# ChannelDriver.net
KiCad netlist of a schematic drawn in Altium Designer
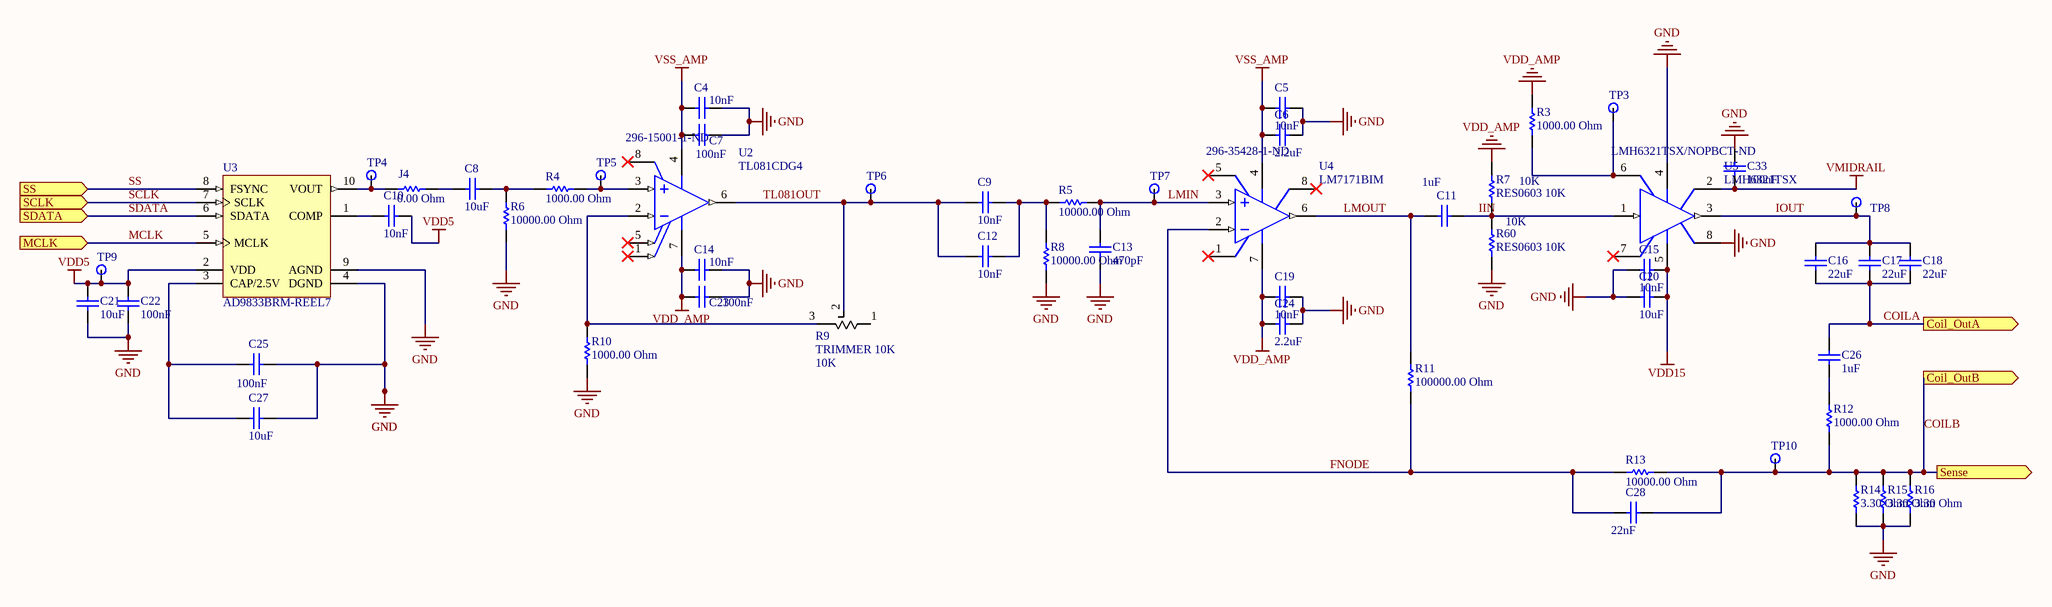
[diagram p0: ChannelDriver.SchDoc]

(export (version "E")
  (design (tool "Eeschema 10.0.6"))
  (components
    (comp (ref "C4")
      (value "10nF")
      (footprint "CAPC0603(1608)100_N")
      (description "CAP 10nF 25V ±10% 0603 (1608 Metric) Thickness 1mm SMD")
      (fields (field (name "TOLERANCE") "Â±10%") (field (name "Comment") "CAP 10nF 25V 0603(1608)"))
      (libsource (lib "Altium Content Vault") (part "CMP-1035-02317-1"))
    )
    (comp (ref "C5")
      (value "10nF")
      (footprint "CAPC0603(1608)100_N")
      (description "CAP 10nF 25V ±10% 0603 (1608 Metric) Thickness 1mm SMD")
      (fields (field (name "TOLERANCE") "Â±10%") (field (name "Comment") "CAP 10nF 25V 0603(1608)"))
      (libsource (lib "Altium Content Vault") (part "CMP-1035-02317-1"))
    )
    (comp (ref "C6")
      (value "2.2uF")
      (footprint "CAPC0603(1608)100_M")
      (description "CAP 2.2uF 25V ±10% 0603 (1608 Metric) Thickness 1mm SMD")
      (fields (field (name "TOLERANCE") "Â±10%") (field (name "MANUFACTURER") "Taiyo Yuden"))
      (libsource (lib "Altium Content Vault") (part "CMP-1035-02767-1"))
    )
    (comp (ref "C7")
      (value "100nF")
      (footprint "CAPC0603(1608)100_M")
      (description "CAP 100nF 25V ±10% 0603 (1608 Metric) Thickness 1mm SMD")
      (fields (field (name "TOLERANCE") "Â±10%") (field (name "Comment") "CAP 100nF 25V 0603(1608)"))
      (libsource (lib "Altium Content Vault") (part "CMP-1035-02588-1"))
    )
    (comp (ref "C8")
      (value "10uF")
      (footprint "CAPC1206(3216)190_L")
      (description "CAP 10uF 25V ±10% 1206 (3216 Metric) Thickness 1.9mm SMD")
      (fields (field (name "TOLERANCE") "Â±10%") (field (name "Comment") "CAP 10uF 25V 1206(3216)"))
      (libsource (lib "Altium Content Vault") (part "CMP-1037-04979-1"))
    )
    (comp (ref "C9")
      (value "10nF")
      (footprint "CAPC0603(1608)100_N")
      (description "CAP 10nF 25V ±10% 0603 (1608 Metric) Thickness 1mm SMD")
      (fields (field (name "TOLERANCE") "Â±10%") (field (name "Comment") "CAP 10nF 25V 0603(1608)"))
      (libsource (lib "Altium Content Vault") (part "CMP-1035-02317-1"))
    )
    (comp (ref "C10")
      (value "10nF")
      (footprint "CAPC0603(1608)100_N")
      (description "CAP 10nF 25V ±10% 0603 (1608 Metric) Thickness 1mm SMD")
      (fields (field (name "TOLERANCE") "Â±10%") (field (name "Comment") "CAP 10nF 25V 0603(1608)"))
      (libsource (lib "Altium Content Vault") (part "CMP-1035-02317-1"))
    )
    (comp (ref "C11")
      (value "1uF")
      (footprint "CAPC0603(1608)100_L")
      (description "CAP 1uF 25V ±10% 0603 (1608 Metric) Thickness 1mm SMD")
      (fields (field (name "TOLERANCE") "Â±10%") (field (name "Comment") "CAP 1uF 25V 0603(1608)"))
      (libsource (lib "Altium Content Vault") (part "CMP-1035-02740-1"))
    )
    (comp (ref "C12")
      (value "10nF")
      (footprint "CAPC0603(1608)100_N")
      (description "CAP 10nF 25V ±10% 0603 (1608 Metric) Thickness 1mm SMD")
      (fields (field (name "TOLERANCE") "Â±10%") (field (name "Comment") "CAP 10nF 25V 0603(1608)"))
      (libsource (lib "Altium Content Vault") (part "CMP-1035-02317-1"))
    )
    (comp (ref "C13")
      (value "470pF")
      (footprint "CAPC0603(1608)100_N")
      (description "CAP 470pF 25V ±10% 0603 (1608 Metric) Thickness 1mm SMD")
      (fields (field (name "TOLERANCE") "Â±10%") (field (name "MANUFACTURER") "KEMET"))
      (libsource (lib "Altium Content Vault") (part "CMP-1035-01671-1"))
    )
    (comp (ref "C14")
      (value "10nF")
      (footprint "CAPC0603(1608)100_N")
      (description "CAP 10nF 25V ±10% 0603 (1608 Metric) Thickness 1mm SMD")
      (fields (field (name "TOLERANCE") "Â±10%") (field (name "Comment") "CAP 10nF 25V 0603(1608)"))
      (libsource (lib "Altium Content Vault") (part "CMP-1035-02317-1"))
    )
    (comp (ref "C15")
      (value "10nF")
      (footprint "CAPC0603(1608)100_N")
      (description "CAP 10nF 25V ±10% 0603 (1608 Metric) Thickness 1mm SMD")
      (fields (field (name "TOLERANCE") "Â±10%") (field (name "Comment") "CAP 10nF 25V 0603(1608)"))
      (libsource (lib "Altium Content Vault") (part "CMP-1035-02317-1"))
    )
    (comp (ref "C16")
      (value "22uF")
      (footprint "CAPC1206(3216)190_M")
      (description "CAP 22uF 25V ±20% 1206 (3216 Metric) Thickness 1.9mm SMD")
      (fields (field (name "TOLERANCE") "Â±20%") (field (name "Comment") "CAP 22uF 25V 1206(3216)"))
      (libsource (lib "Altium Content Vault") (part "CMP-1037-04995-1"))
    )
    (comp (ref "C17")
      (value "22uF")
      (footprint "CAPC1206(3216)190_M")
      (description "CAP 22uF 25V ±20% 1206 (3216 Metric) Thickness 1.9mm SMD")
      (fields (field (name "TOLERANCE") "Â±20%") (field (name "Comment") "CAP 22uF 25V 1206(3216)"))
      (libsource (lib "Altium Content Vault") (part "CMP-1037-04995-1"))
    )
    (comp (ref "C18")
      (value "22uF")
      (footprint "CAPC1206(3216)190_M")
      (description "CAP 22uF 25V ±20% 1206 (3216 Metric) Thickness 1.9mm SMD")
      (fields (field (name "TOLERANCE") "Â±20%") (field (name "Comment") "CAP 22uF 25V 1206(3216)"))
      (libsource (lib "Altium Content Vault") (part "CMP-1037-04995-1"))
    )
    (comp (ref "C19")
      (value "10nF")
      (footprint "CAPC0603(1608)100_N")
      (description "CAP 10nF 25V ±10% 0603 (1608 Metric) Thickness 1mm SMD")
      (fields (field (name "TOLERANCE") "Â±10%") (field (name "Comment") "CAP 10nF 25V 0603(1608)"))
      (libsource (lib "Altium Content Vault") (part "CMP-1035-02317-1"))
    )
    (comp (ref "C20")
      (value "10uF")
      (footprint "CAPC1206(3216)190_L")
      (description "CAP 10uF 25V ±10% 1206 (3216 Metric) Thickness 1.9mm SMD")
      (fields (field (name "TOLERANCE") "Â±10%") (field (name "Comment") "CAP 10uF 25V 1206(3216)"))
      (libsource (lib "Altium Content Vault") (part "CMP-1037-04979-1"))
    )
    (comp (ref "C21")
      (value "10uF")
      (footprint "CAPC1206(3216)190_L")
      (description "CAP 10uF 25V ±10% 1206 (3216 Metric) Thickness 1.9mm SMD")
      (fields (field (name "TOLERANCE") "Â±10%") (field (name "Comment") "CAP 10uF 25V 1206(3216)"))
      (libsource (lib "Altium Content Vault") (part "CMP-1037-04979-1"))
    )
    (comp (ref "C22")
      (value "100nF")
      (footprint "CAPC0603(1608)100_M")
      (description "CAP 100nF 25V ±10% 0603 (1608 Metric) Thickness 1mm SMD")
      (fields (field (name "TOLERANCE") "Â±10%") (field (name "Comment") "CAP 100nF 25V 0603(1608)"))
      (libsource (lib "Altium Content Vault") (part "CMP-1035-02588-1"))
    )
    (comp (ref "C23")
      (value "100nF")
      (footprint "CAPC0603(1608)100_M")
      (description "CAP 100nF 25V ±10% 0603 (1608 Metric) Thickness 1mm SMD")
      (fields (field (name "TOLERANCE") "Â±10%") (field (name "Comment") "CAP 100nF 25V 0603(1608)"))
      (libsource (lib "Altium Content Vault") (part "CMP-1035-02588-1"))
    )
    (comp (ref "C24")
      (value "2.2uF")
      (footprint "CAPC0603(1608)100_M")
      (description "CAP 2.2uF 25V ±10% 0603 (1608 Metric) Thickness 1mm SMD")
      (fields (field (name "TOLERANCE") "Â±10%") (field (name "MANUFACTURER") "Taiyo Yuden"))
      (libsource (lib "Altium Content Vault") (part "CMP-1035-02767-1"))
    )
    (comp (ref "C25")
      (value "100nF")
      (footprint "CAPC0603(1608)100_M")
      (description "CAP 100nF 25V ±10% 0603 (1608 Metric) Thickness 1mm SMD")
      (fields (field (name "TOLERANCE") "Â±10%") (field (name "Comment") "CAP 100nF 25V 0603(1608)"))
      (libsource (lib "Altium Content Vault") (part "CMP-1035-02588-1"))
    )
    (comp (ref "C26")
      (value "1uF")
      (footprint "CAPC0603(1608)100_L")
      (description "CAP 1uF 25V ±10% 0603 (1608 Metric) Thickness 1mm SMD")
      (fields (field (name "TOLERANCE") "Â±10%") (field (name "Comment") "CAP 1uF 25V 0603(1608)"))
      (libsource (lib "Altium Content Vault") (part "CMP-1035-02740-1"))
    )
    (comp (ref "C27")
      (value "10uF")
      (footprint "CAPC1206(3216)190_L")
      (description "CAP 10uF 25V ±10% 1206 (3216 Metric) Thickness 1.9mm SMD")
      (fields (field (name "TOLERANCE") "Â±10%") (field (name "Comment") "CAP 10uF 25V 1206(3216)"))
      (libsource (lib "Altium Content Vault") (part "CMP-1037-04979-1"))
    )
    (comp (ref "C28")
      (value "22nF")
      (footprint "CAPC0603(1608)100_N")
      (description "CAP 10nF 25V ±10% 0603 (1608 Metric) Thickness 1mm SMD")
      (fields (field (name "TOLERANCE") "Â±10%") (field (name "MANUFACTURER") "Taiyo Yuden"))
      (libsource (lib "Altium Content Vault") (part "CMP-1035-02317-1"))
    )
    (comp (ref "C33")
      (value "100nF")
      (footprint "CAPC0603(1608)100_M")
      (description "CAP 100nF 25V ±10% 0603 (1608 Metric) Thickness 1mm SMD")
      (fields (field (name "TOLERANCE") "Â±10%") (field (name "Comment") "CAP 100nF 25V 0603(1608)"))
      (libsource (lib "Altium Content Vault") (part "CMP-1035-02588-1"))
    )
    (comp (ref "J4")
      (value "0.00 Ohm")
      (footprint "RESC1206(3216)_M")
      (description "Jumper 1206 (3216 Metric)")
      (fields (field (name "TOLERANCE") "None"))
      (libsource (lib "Altium Content Vault") (part "CMP-1014-00001-1"))
    )
    (comp (ref "R3")
      (value "1000.00 Ohm")
      (footprint "RESC0603(1608)_L")
      (description "1K 0.1W 5% 0603 (1608 Metric)  SMD")
      (fields (field (name "TOLERANCE") "5 %") (field (name "POWER") "0.1 W"))
      (libsource (lib "Altium Content Vault") (part "CMP-1012-00074-1"))
    )
    (comp (ref "R4")
      (value "1000.00 Ohm")
      (footprint "RESC0603(1608)_L")
      (description "1K 0.1W 5% 0603 (1608 Metric)  SMD")
      (fields (field (name "TOLERANCE") "5 %") (field (name "POWER") "0.1 W"))
      (libsource (lib "Altium Content Vault") (part "CMP-1012-00074-1"))
    )
    (comp (ref "R5")
      (value "10000.00 Ohm")
      (footprint "RESC0603(1608)_N")
      (description "10K 0.1W 5% 0603 (1608 Metric)  SMD")
      (fields (field (name "TOLERANCE") "5 %") (field (name "POWER") "0.1 W"))
      (libsource (lib "Altium Content Vault") (part "CMP-1012-00098-1"))
    )
    (comp (ref "R6")
      (value "10000.00 Ohm")
      (footprint "RESC0603(1608)_N")
      (description "10K 0.1W 5% 0603 (1608 Metric)  SMD")
      (fields (field (name "TOLERANCE") "5 %") (field (name "POWER") "0.1 W"))
      (libsource (lib "Altium Content Vault") (part "CMP-1012-00098-1"))
    )
    (comp (ref "R7")
      (value "RES0603 10K")
      (footprint "RESC0603(1608)_L")
      (description "0603 (1608 Metric) Chip Resistor")
      (fields
        (field (name "ALTIUM_VALUE") "10K")
        (field (name "MANUFACTURER") "Yageo")
        (field (name "MANUFACTURER PART NUMBER") "RT0603BRD0710KL")
      )
      (libsource (lib "Altium Content Vault") (part "CMP-1591-00001-1"))
    )
    (comp (ref "R8")
      (value "10000.00 Ohm")
      (footprint "RESC0603(1608)_N")
      (description "10K 0.1W 5% 0603 (1608 Metric)  SMD")
      (fields (field (name "TOLERANCE") "5 %") (field (name "POWER") "0.1 W"))
      (libsource (lib "Altium Content Vault") (part "CMP-1012-00098-1"))
    )
    (comp (ref "R9")
      (value "TRIMMER 10K")
      (footprint "TRIMMER 10K")
      (description "TRIMMER 10K OHM 0.5W TH")
      (fields
        (field (name "MANUFACTURER") "TE Connectivity Passive Product")
        (field (name "MANUFACTURER PART NUMBER") "1-1623849-0")
        (field (name "ALTIUM_VALUE") "10K")
        (field (name "PUBLISHER") "Altium Limited")
      )
      (libsource (lib "AnserEMT") (part "TRIMMER 10K"))
    )
    (comp (ref "R10")
      (value "1000.00 Ohm")
      (footprint "RESC0603(1608)_L")
      (description "1K 0.1W 5% 0603 (1608 Metric)  SMD")
      (fields (field (name "TOLERANCE") "5 %") (field (name "POWER") "0.1 W"))
      (libsource (lib "Altium Content Vault") (part "CMP-1012-00074-1"))
    )
    (comp (ref "R11")
      (value "100000.00 Ohm")
      (footprint "RESC0603(1608)_N")
      (description "100K 0.1W 5% 0603 (1608 Metric)  SMD")
      (fields (field (name "TOLERANCE") "5 %") (field (name "POWER") "0.1 W"))
      (libsource (lib "Altium Content Vault") (part "CMP-1012-00122-1"))
    )
    (comp (ref "R12")
      (value "1000.00 Ohm")
      (footprint "RESC0603(1608)_L")
      (description "1K 0.1W 5% 0603 (1608 Metric)  SMD")
      (fields (field (name "TOLERANCE") "5 %") (field (name "POWER") "0.1 W"))
      (libsource (lib "Altium Content Vault") (part "CMP-1012-00074-1"))
    )
    (comp (ref "R13")
      (value "10000.00 Ohm")
      (footprint "RESC0603(1608)_N")
      (description "10K 0.1W 5% 0603 (1608 Metric)  SMD")
      (fields (field (name "TOLERANCE") "5 %") (field (name "POWER") "0.1 W"))
      (libsource (lib "Altium Content Vault") (part "CMP-1012-00098-1"))
    )
    (comp (ref "R14")
      (value "3.30 Ohm")
      (footprint "RESC1206(3216)_N")
      (description "3R3 0.25W 5% 1206 (3216 Metric)  SMD")
      (fields (field (name "POWER") "0.25 W") (field (name "TOLERANCE") "5 %"))
      (libsource (lib "Altium Content Vault") (part "CMP-1014-00014-1"))
    )
    (comp (ref "R15")
      (value "3.30 Ohm")
      (footprint "RESC1206(3216)_N")
      (description "3R3 0.25W 5% 1206 (3216 Metric)  SMD")
      (fields (field (name "POWER") "0.25 W") (field (name "TOLERANCE") "5 %"))
      (libsource (lib "Altium Content Vault") (part "CMP-1014-00014-1"))
    )
    (comp (ref "R16")
      (value "3.30 Ohm")
      (footprint "RESC1206(3216)_N")
      (description "3R3 0.25W 5% 1206 (3216 Metric)  SMD")
      (fields (field (name "POWER") "0.25 W") (field (name "TOLERANCE") "5 %"))
      (libsource (lib "Altium Content Vault") (part "CMP-1014-00014-1"))
    )
    (comp (ref "R60")
      (value "RES0603 10K")
      (footprint "RESC0603(1608)_L")
      (description "0603 (1608 Metric) Chip Resistor")
      (fields
        (field (name "ALTIUM_VALUE") "10K")
        (field (name "MANUFACTURER") "Yageo")
        (field (name "MANUFACTURER PART NUMBER") "RT0603BRD0710KL")
      )
      (libsource (lib "Altium Content Vault") (part "CMP-1591-00001-1"))
    )
    (comp (ref "TP3")
      (value "Testpoint")
      (footprint "0603 PROBE PAD")
      (description "0.063\" x 0.031\" x 0.045\" (1.60mm x 0.80mm x 1.15mm)")
      (libsource (lib "testpoint") (part "Testpoint"))
    )
    (comp (ref "TP4")
      (value "Testpoint")
      (footprint "0603 PROBE PAD")
      (description "0.063\" x 0.031\" x 0.045\" (1.60mm x 0.80mm x 1.15mm)")
      (libsource (lib "testpoint") (part "Testpoint"))
    )
    (comp (ref "TP5")
      (value "Testpoint")
      (footprint "0603 PROBE PAD")
      (description "0.063\" x 0.031\" x 0.045\" (1.60mm x 0.80mm x 1.15mm)")
      (libsource (lib "testpoint") (part "Testpoint"))
    )
    (comp (ref "TP6")
      (value "Testpoint")
      (footprint "0603 PROBE PAD")
      (description "0.063\" x 0.031\" x 0.045\" (1.60mm x 0.80mm x 1.15mm)")
      (libsource (lib "testpoint") (part "Testpoint"))
    )
    (comp (ref "TP7")
      (value "Testpoint")
      (footprint "0603 PROBE PAD")
      (description "0.063\" x 0.031\" x 0.045\" (1.60mm x 0.80mm x 1.15mm)")
      (libsource (lib "testpoint") (part "Testpoint"))
    )
    (comp (ref "TP8")
      (value "Testpoint")
      (footprint "0603 PROBE PAD")
      (description "0.063\" x 0.031\" x 0.045\" (1.60mm x 0.80mm x 1.15mm)")
      (libsource (lib "testpoint") (part "Testpoint"))
    )
    (comp (ref "TP9")
      (value "Testpoint")
      (footprint "0603 PROBE PAD")
      (description "0.063\" x 0.031\" x 0.045\" (1.60mm x 0.80mm x 1.15mm)")
      (libsource (lib "testpoint") (part "Testpoint"))
    )
    (comp (ref "TP10")
      (value "Testpoint")
      (footprint "0603 PROBE PAD")
      (description "0.063\" x 0.031\" x 0.045\" (1.60mm x 0.80mm x 1.15mm)")
      (libsource (lib "testpoint") (part "Testpoint"))
    )
    (comp (ref "U2")
      (value "TL081CDG4")
      (footprint "TI-D8_N")
      (fields
        (field (name "MANUFACTURER") "Texas Instruments")
        (field (name "SUPPLIER PART NUMBER 1") "296-15001-1-ND")
        (field (name "MANUFACTURER PART NUMBER") "TL081CDR")
      )
      (libsource (lib "Altium Content Vault") (part "CMP-0017-00506-1"))
    )
    (comp (ref "U3")
      (value "AD9833BRM-REEL7")
      (footprint "ADI-RM-10_L")
      (fields
        (field (name "MANUFACTURER") "Analog Devices Inc.")
        (field (name "MANUFACTURER PART NUMBER") "AD9833BRMZ-REEL7")
      )
      (libsource (lib "Altium Content Vault") (part "CMP-0293-00080-1"))
    )
    (comp (ref "U4")
      (value "LM7171BIM")
      (footprint "D0008A_L")
      (description "Very High Speed, High Output Current, Voltage Feedback Amplifier, 8-pin Narrow SOIC")
      (fields
        (field (name "MANUFACTURER") "Texas Instruments")
        (field (name "SUPPLIER PART NUMBER 1") "296-35428-1-ND")
        (field (name "MANUFACTURER PART NUMBER") "LM7171AIMX/NOPB")
      )
      (libsource (lib "Altium Content Vault") (part "CMP-0055-00670-3"))
    )
    (comp (ref "U5")
      (value "LMH6321TSX")
      (footprint "TS7B_N")
      (description "300 mA High Speed Buffer with Adjustable Current Limit, 7-pin TO-263")
      (fields
        (field (name "MANUFACTURER") "National Semiconductor")
        (field (name "SUPPLIER PART NUMBER 1") "LMH6321TSX/NOPBCT-ND")
        (field (name "MANUFACTURER PART NUMBER") "LMH6321TSX/NOPB")
      )
      (libsource (lib "Altium Content Vault") (part "CMP-0055-00076-2"))
    )
  )
  (nets
    (net (code "1") (name "/COILA") (class "Default")
      (node (ref "C16") (pin "2") (pinfunction "2_2") (pintype "passive"))
      (node (ref "C17") (pin "2") (pinfunction "2_2") (pintype "passive"))
      (node (ref "C18") (pin "2") (pinfunction "2_2") (pintype "passive"))
      (node (ref "C26") (pin "2") (pinfunction "2_2") (pintype "passive"))
    )
    (net (code "2") (name "/COILB") (class "Default")
      (node (ref "C28") (pin "2") (pinfunction "2_2") (pintype "passive"))
      (node (ref "R12") (pin "2") (pinfunction "2_2") (pintype "passive"))
      (node (ref "R13") (pin "1") (pinfunction "1_1") (pintype "passive"))
      (node (ref "R14") (pin "2") (pinfunction "2_2") (pintype "passive"))
      (node (ref "R15") (pin "2") (pinfunction "2_2") (pintype "passive"))
      (node (ref "R16") (pin "2") (pinfunction "2_2") (pintype "passive"))
      (node (ref "TP10") (pin "0") (pintype "passive"))
    )
    (net (code "3") (name "/FNODE") (class "Default")
      (node (ref "C28") (pin "1") (pinfunction "1_1") (pintype "passive"))
      (node (ref "R11") (pin "2") (pinfunction "2_2") (pintype "passive"))
      (node (ref "R13") (pin "2") (pinfunction "2_2") (pintype "passive"))
      (node (ref "U4") (pin "2") (pinfunction "IN-_2") (pintype "input"))
    )
    (net (code "4") (name "/IIN") (class "Default")
      (node (ref "C11") (pin "2") (pinfunction "2_2") (pintype "passive"))
      (node (ref "R60") (pin "2") (pinfunction "2_2") (pintype "passive"))
      (node (ref "R7") (pin "1") (pinfunction "1_1") (pintype "passive"))
      (node (ref "U5") (pin "1") (pinfunction "IN_1") (pintype "input"))
    )
    (net (code "5") (name "/IOUT") (class "Default")
      (node (ref "C16") (pin "1") (pinfunction "1_1") (pintype "passive"))
      (node (ref "C17") (pin "1") (pinfunction "1_1") (pintype "passive"))
      (node (ref "C18") (pin "1") (pinfunction "1_1") (pintype "passive"))
      (node (ref "TP8") (pin "0") (pintype "passive"))
      (node (ref "U5") (pin "3") (pinfunction "OUT_3") (pintype "output"))
    )
    (net (code "6") (name "/LMIN") (class "Default")
      (node (ref "C13") (pin "2") (pinfunction "2_2") (pintype "passive"))
      (node (ref "R5") (pin "1") (pinfunction "1_1") (pintype "passive"))
      (node (ref "TP7") (pin "0") (pintype "passive"))
      (node (ref "U4") (pin "3") (pinfunction "IN+_3") (pintype "input"))
    )
    (net (code "7") (name "/LMOUT") (class "Default")
      (node (ref "C11") (pin "1") (pinfunction "1_1") (pintype "passive"))
      (node (ref "R11") (pin "1") (pinfunction "1_1") (pintype "passive"))
      (node (ref "U4") (pin "6") (pinfunction "OUT_6") (pintype "output"))
    )
    (net (code "8") (name "/MCLK") (class "Default")
      (node (ref "U3") (pin "5") (pinfunction "MCLK_5") (pintype "input"))
    )
    (net (code "9") (name "/SCLK") (class "Default")
      (node (ref "U3") (pin "7") (pinfunction "SCLK_7") (pintype "input"))
    )
    (net (code "10") (name "/SDATA") (class "Default")
      (node (ref "U3") (pin "6") (pinfunction "SDATA_6") (pintype "input"))
    )
    (net (code "11") (name "/SS") (class "Default")
      (node (ref "U3") (pin "8") (pinfunction "FSYNC_8") (pintype "input"))
    )
    (net (code "12") (name "/TL081OUT") (class "Default")
      (node (ref "C12") (pin "1") (pinfunction "1_1") (pintype "passive"))
      (node (ref "C9") (pin "1") (pinfunction "1_1") (pintype "passive"))
      (node (ref "R9") (pin "2") (pinfunction "2_2") (pintype "passive"))
      (node (ref "TP6") (pin "0") (pintype "passive"))
      (node (ref "U2") (pin "6") (pinfunction "OUT_6") (pintype "output"))
    )
    (net (code "13") (name "GND") (class "Default")
      (node (ref "C13") (pin "1") (pinfunction "1_1") (pintype "passive"))
      (node (ref "C14") (pin "2") (pinfunction "2_2") (pintype "passive"))
      (node (ref "C15") (pin "1") (pinfunction "1_1") (pintype "passive"))
      (node (ref "C19") (pin "2") (pinfunction "2_2") (pintype "passive"))
      (node (ref "C20") (pin "2") (pinfunction "2_2") (pintype "passive"))
      (node (ref "C21") (pin "1") (pinfunction "1_1") (pintype "passive"))
      (node (ref "C22") (pin "2") (pinfunction "2_2") (pintype "passive"))
      (node (ref "C23") (pin "1") (pinfunction "1_1") (pintype "passive"))
      (node (ref "C24") (pin "2") (pinfunction "2_2") (pintype "passive"))
      (node (ref "C25") (pin "1") (pinfunction "1_1") (pintype "passive"))
      (node (ref "C27") (pin "1") (pinfunction "1_1") (pintype "passive"))
      (node (ref "C33") (pin "1") (pinfunction "1_1") (pintype "passive"))
      (node (ref "C4") (pin "2") (pinfunction "2_2") (pintype "passive"))
      (node (ref "C5") (pin "2") (pinfunction "2_2") (pintype "passive"))
      (node (ref "C6") (pin "2") (pinfunction "2_2") (pintype "passive"))
      (node (ref "C7") (pin "1") (pinfunction "1_1") (pintype "passive"))
      (node (ref "R10") (pin "2") (pinfunction "2_2") (pintype "passive"))
      (node (ref "R14") (pin "1") (pinfunction "1_1") (pintype "passive"))
      (node (ref "R15") (pin "1") (pinfunction "1_1") (pintype "passive"))
      (node (ref "R16") (pin "1") (pinfunction "1_1") (pintype "passive"))
      (node (ref "R6") (pin "2") (pinfunction "2_2") (pintype "passive"))
      (node (ref "R60") (pin "1") (pinfunction "1_1") (pintype "passive"))
      (node (ref "R8") (pin "2") (pinfunction "2_2") (pintype "passive"))
      (node (ref "U3") (pin "4") (pinfunction "DGND_4") (pintype "power_in"))
      (node (ref "U3") (pin "9") (pinfunction "AGND_9") (pintype "power_in"))
      (node (ref "U5") (pin "4") (pinfunction "V-_4") (pintype "power_in"))
      (node (ref "U5") (pin "8") (pinfunction "TAB_8") (pintype "passive"))
    )
    (net (code "14") (name "Net-(C8-Pad1)") (class "Default")
      (node (ref "C8") (pin "1") (pinfunction "1_1") (pintype "passive"))
      (node (ref "R4") (pin "2") (pinfunction "2_2") (pintype "passive"))
      (node (ref "R6") (pin "1") (pinfunction "1_1") (pintype "passive"))
    )
    (net (code "15") (name "Net-(C8-Pad2)") (class "Default")
      (node (ref "C8") (pin "2") (pinfunction "2_2") (pintype "passive"))
      (node (ref "J4") (pin "2") (pinfunction "2_2") (pintype "passive"))
    )
    (net (code "16") (name "Net-(C12-Pad2)") (class "Default")
      (node (ref "C12") (pin "2") (pinfunction "2_2") (pintype "passive"))
      (node (ref "C9") (pin "2") (pinfunction "2_2") (pintype "passive"))
      (node (ref "R5") (pin "2") (pinfunction "2_2") (pintype "passive"))
      (node (ref "R8") (pin "1") (pinfunction "1_1") (pintype "passive"))
    )
    (net (code "17") (name "Net-(C26-Pad1)") (class "Default")
      (node (ref "C26") (pin "1") (pinfunction "1_1") (pintype "passive"))
      (node (ref "R12") (pin "1") (pinfunction "1_1") (pintype "passive"))
    )
    (net (code "18") (name "Net-(U2-IN+)") (class "Default")
      (node (ref "R4") (pin "1") (pinfunction "1_1") (pintype "passive"))
      (node (ref "TP5") (pin "0") (pintype "passive"))
      (node (ref "U2") (pin "3") (pinfunction "IN+_3") (pintype "input"))
    )
    (net (code "19") (name "Net-(U2-IN-)") (class "Default")
      (node (ref "R10") (pin "1") (pinfunction "1_1") (pintype "passive"))
      (node (ref "R9") (pin "3") (pinfunction "3_3") (pintype "passive"))
      (node (ref "U2") (pin "2") (pinfunction "IN-_2") (pintype "input"))
    )
    (net (code "20") (name "Net-(U3-CAP{slash}2.5V)") (class "Default")
      (node (ref "C25") (pin "2") (pinfunction "2_2") (pintype "passive"))
      (node (ref "C27") (pin "2") (pinfunction "2_2") (pintype "passive"))
      (node (ref "U3") (pin "3") (pinfunction "CAP/2.5V_3") (pintype "power_in"))
    )
    (net (code "21") (name "Net-(U3-COMP)") (class "Default")
      (node (ref "C10") (pin "1") (pinfunction "1_1") (pintype "passive"))
      (node (ref "U3") (pin "1") (pinfunction "COMP_1") (pintype "passive"))
    )
    (net (code "22") (name "Net-(U3-VOUT)") (class "Default")
      (node (ref "J4") (pin "1") (pinfunction "1_1") (pintype "passive"))
      (node (ref "TP4") (pin "0") (pintype "passive"))
      (node (ref "U3") (pin "10") (pinfunction "VOUT_10") (pintype "output"))
    )
    (net (code "23") (name "Net-(U5-EF)") (class "Default")
      (node (ref "R3") (pin "2") (pinfunction "2_2") (pintype "passive"))
      (node (ref "TP3") (pin "0") (pintype "passive"))
      (node (ref "U5") (pin "6") (pinfunction "EF_6") (pintype "passive"))
    )
    (net (code "24") (name "VDD5") (class "Default")
      (node (ref "C10") (pin "2") (pinfunction "2_2") (pintype "passive"))
      (node (ref "C21") (pin "2") (pinfunction "2_2") (pintype "passive"))
      (node (ref "C22") (pin "1") (pinfunction "1_1") (pintype "passive"))
      (node (ref "TP9") (pin "0") (pintype "passive"))
      (node (ref "U3") (pin "2") (pinfunction "VDD_2") (pintype "power_in"))
    )
    (net (code "25") (name "VDD15") (class "Default")
      (node (ref "C15") (pin "2") (pinfunction "2_2") (pintype "passive"))
      (node (ref "C20") (pin "1") (pinfunction "1_1") (pintype "passive"))
      (node (ref "U5") (pin "5") (pinfunction "V+_5") (pintype "power_in"))
    )
    (net (code "26") (name "VDD_AMP") (class "Default")
      (node (ref "C14") (pin "1") (pinfunction "1_1") (pintype "passive"))
      (node (ref "C19") (pin "1") (pinfunction "1_1") (pintype "passive"))
      (node (ref "C23") (pin "2") (pinfunction "2_2") (pintype "passive"))
      (node (ref "C24") (pin "1") (pinfunction "1_1") (pintype "passive"))
      (node (ref "R3") (pin "1") (pinfunction "1_1") (pintype "passive"))
      (node (ref "R7") (pin "2") (pinfunction "2_2") (pintype "passive"))
      (node (ref "U2") (pin "7") (pinfunction "VCC+_7") (pintype "power_in"))
      (node (ref "U4") (pin "7") (pinfunction "V+_7") (pintype "power_in"))
    )
    (net (code "27") (name "VMIDRAIL") (class "Default")
      (node (ref "C33") (pin "2") (pinfunction "2_2") (pintype "passive"))
      (node (ref "U5") (pin "2") (pinfunction "GND_2") (pintype "power_in"))
    )
    (net (code "28") (name "VSS_AMP") (class "Default")
      (node (ref "C4") (pin "1") (pinfunction "1_1") (pintype "passive"))
      (node (ref "C5") (pin "1") (pinfunction "1_1") (pintype "passive"))
      (node (ref "C6") (pin "1") (pinfunction "1_1") (pintype "passive"))
      (node (ref "C7") (pin "2") (pinfunction "2_2") (pintype "passive"))
      (node (ref "U2") (pin "4") (pinfunction "VCC-_4") (pintype "power_in"))
      (node (ref "U4") (pin "4") (pinfunction "V-_4") (pintype "power_in"))
    )
    (net (code "29") (name "unconnected-(R9-Pad1)") (class "Default")
      (node (ref "R9") (pin "1") (pinfunction "1_1") (pintype "passive"))
    )
    (net (code "30") (name "unconnected-(U2-NC-Pad8)") (class "Default")
      (node (ref "U2") (pin "8") (pinfunction "NC_8") (pintype "passive+no_connect"))
    )
    (net (code "31") (name "unconnected-(U2-OFFSET_N1-Pad1)") (class "Default")
      (node (ref "U2") (pin "1") (pinfunction "OFFSET_N1_1") (pintype "input+no_connect"))
    )
    (net (code "32") (name "unconnected-(U2-OFFSET_N2-Pad5)") (class "Default")
      (node (ref "U2") (pin "5") (pinfunction "OFFSET_N2_5") (pintype "input+no_connect"))
    )
    (net (code "33") (name "unconnected-(U4-NC-Pad1)") (class "Default")
      (node (ref "U4") (pin "1") (pinfunction "NC_1") (pintype "passive+no_connect"))
    )
    (net (code "34") (name "unconnected-(U4-NC-Pad5)") (class "Default")
      (node (ref "U4") (pin "5") (pinfunction "NC_5") (pintype "passive+no_connect"))
    )
    (net (code "35") (name "unconnected-(U4-NC-Pad8)") (class "Default")
      (node (ref "U4") (pin "8") (pinfunction "NC_8") (pintype "passive+no_connect"))
    )
    (net (code "36") (name "unconnected-(U5-CL-Pad7)") (class "Default")
      (node (ref "U5") (pin "7") (pinfunction "CL_7") (pintype "passive+no_connect"))
    )
  )
)
